# WAB_1x4_top.net
KiCad netlist of a schematic drawn in Altium Designer
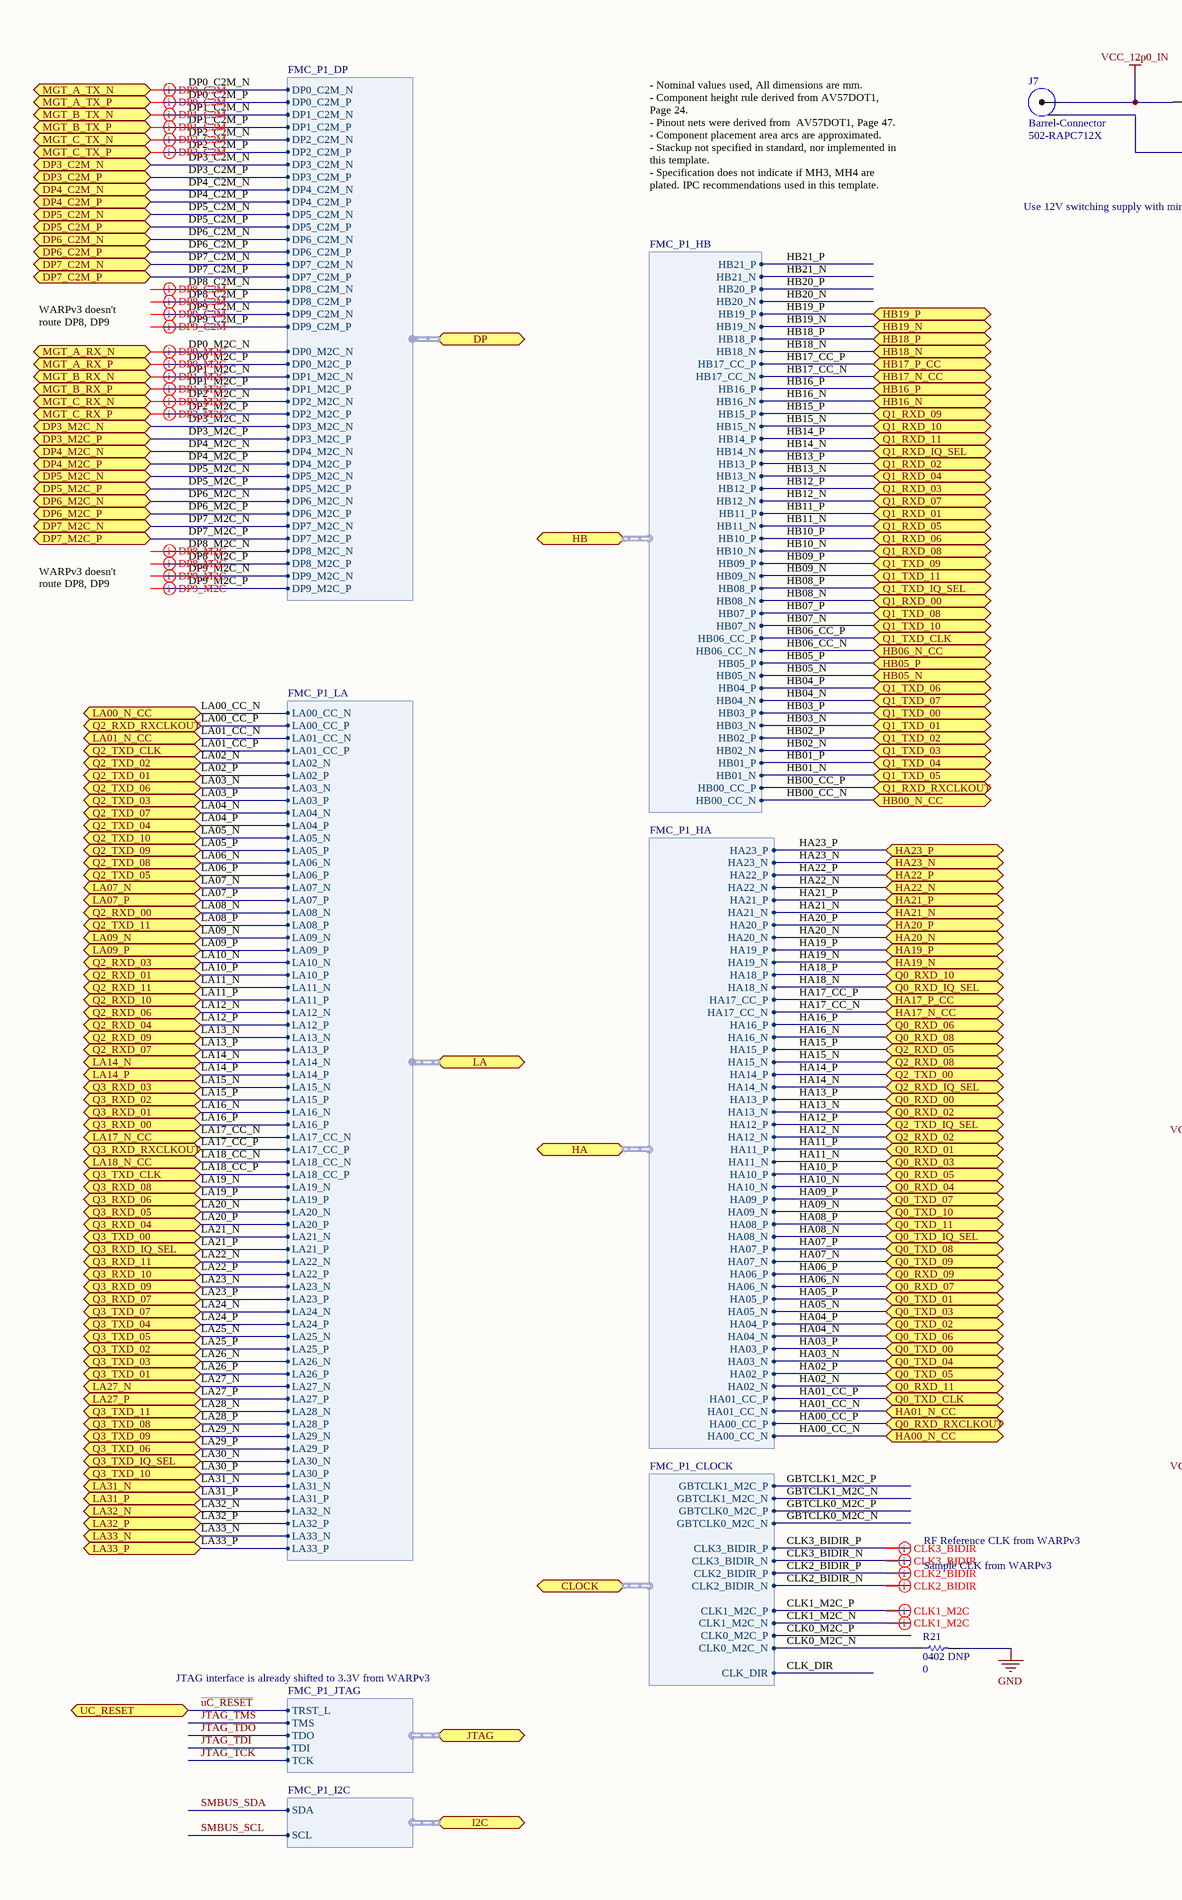
[diagram p0: WAB_1x4_top.SchDoc, left]
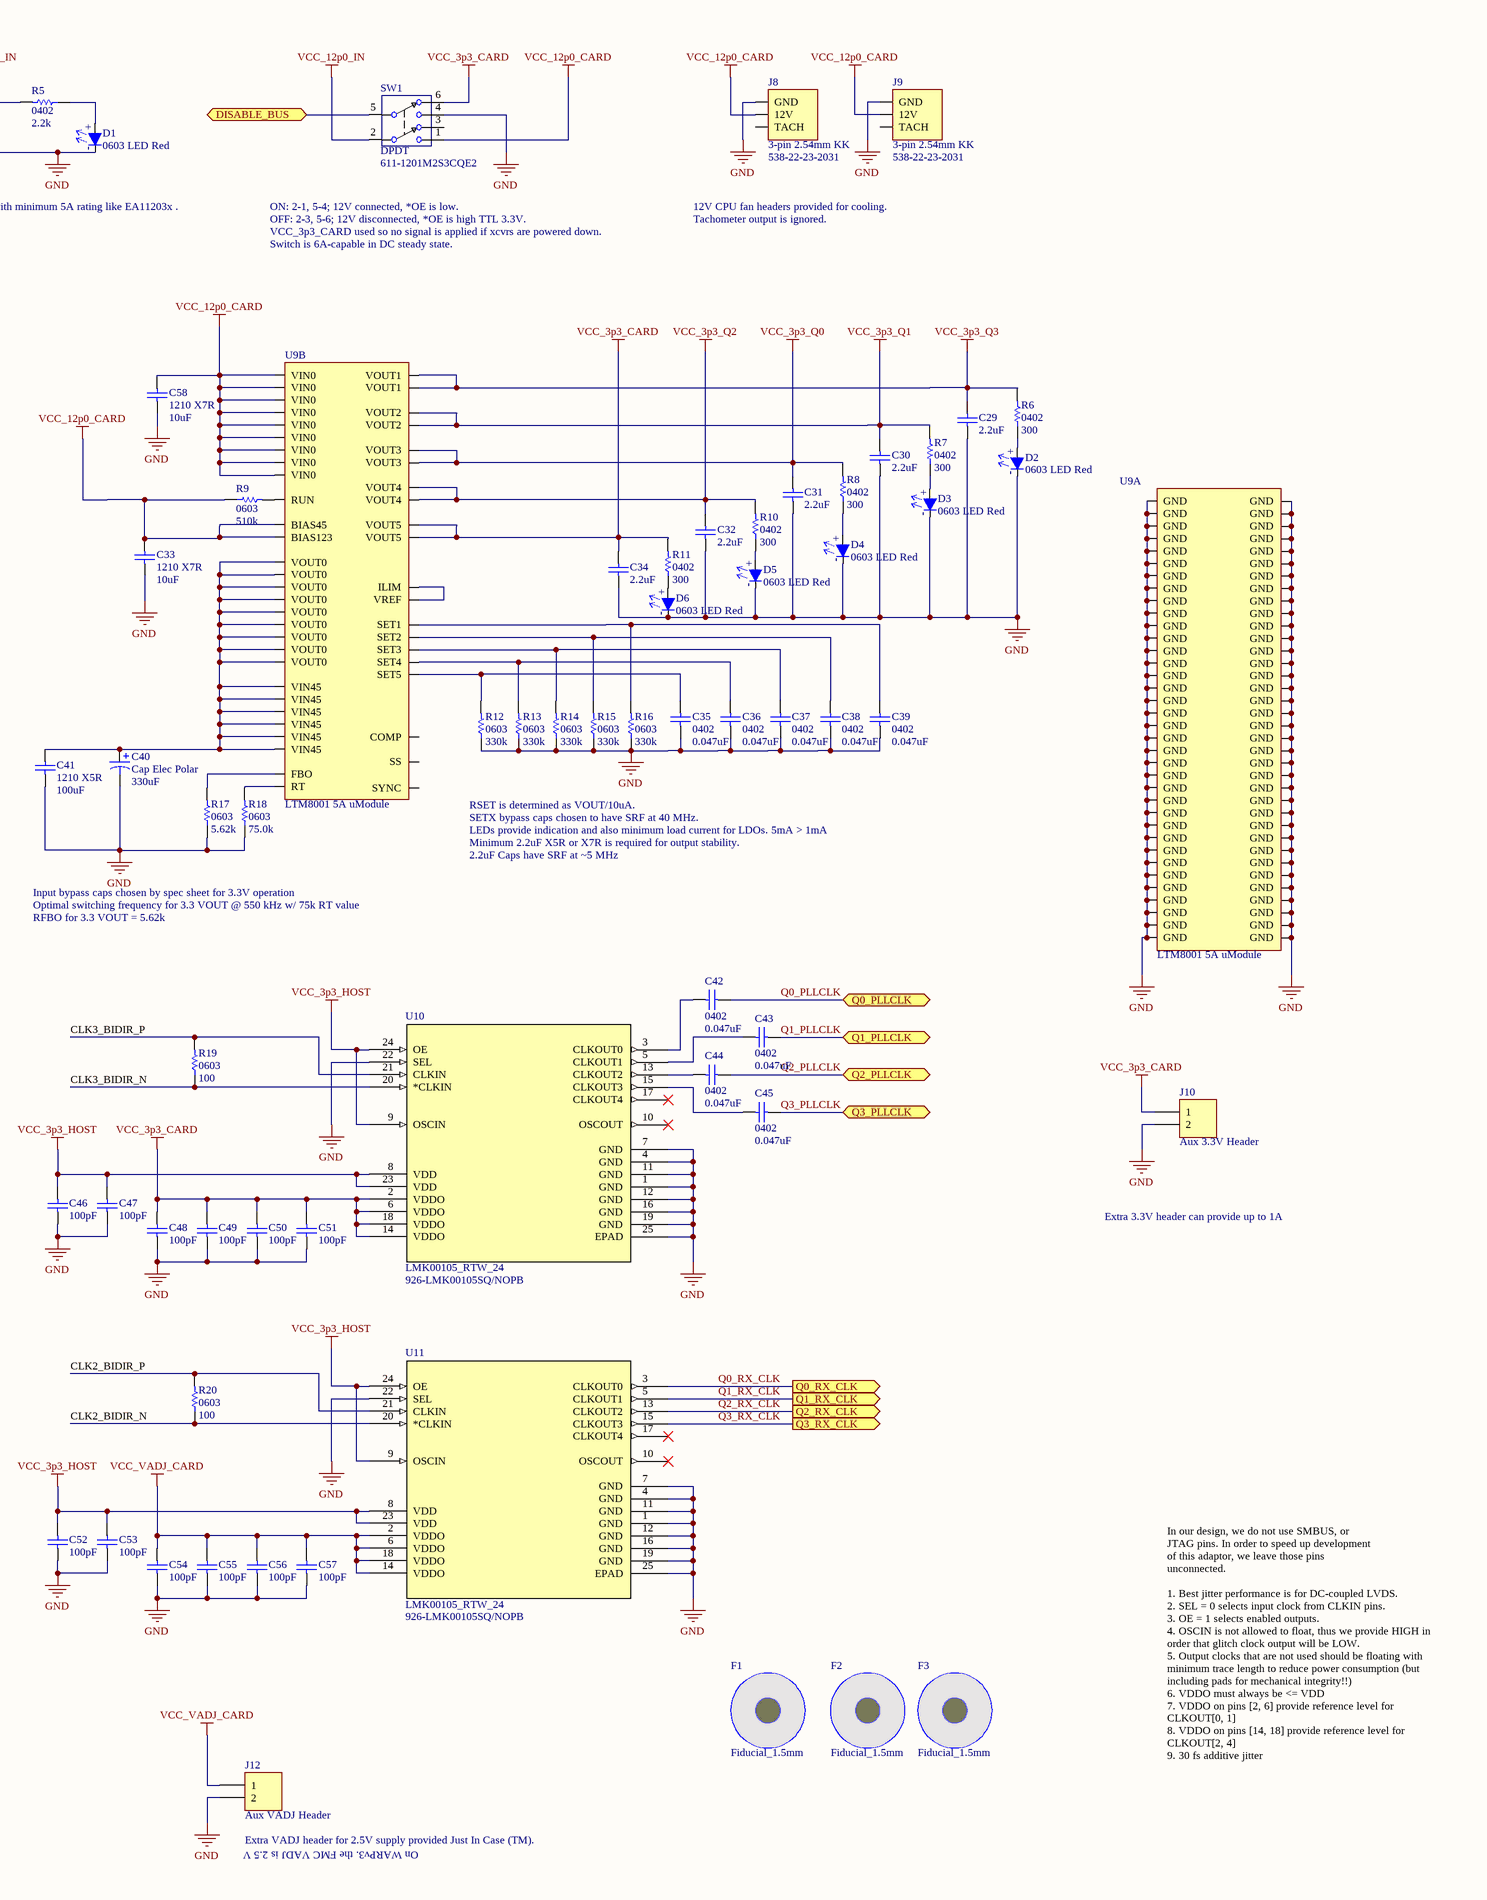
[diagram p1: WAB_1x4_top.SchDoc, right]

(export (version "E")
  (design (tool "Eeschema 10.0.6"))
  (components
    (comp (ref "C29")
      (value "2.2uF")
      (footprint "0402_SMT_CAP")
      (description "0402 SMT Capacitor")
      (fields (field (name "Comment") "0402"))
      (libsource (lib "RNG_Parts") (part "Cap_0402"))
    )
    (comp (ref "C30")
      (value "2.2uF")
      (footprint "0402_SMT_CAP")
      (description "0402 SMT Capacitor")
      (fields (field (name "Comment") "0402"))
      (libsource (lib "RNG_Parts") (part "Cap_0402"))
    )
    (comp (ref "C31")
      (value "2.2uF")
      (footprint "0402_SMT_CAP")
      (description "0402 SMT Capacitor")
      (fields (field (name "Comment") "0402"))
      (libsource (lib "RNG_Parts") (part "Cap_0402"))
    )
    (comp (ref "C32")
      (value "2.2uF")
      (footprint "0402_SMT_CAP")
      (description "0402 SMT Capacitor")
      (fields (field (name "Comment") "0402"))
      (libsource (lib "RNG_Parts") (part "Cap_0402"))
    )
    (comp (ref "C33")
      (value "1210 X7R")
      (footprint "1210_Chip_Cap")
      (description "1210 SMT Capacitor")
      (fields (field (name "ALTIUM_VALUE") "10uF"))
      (libsource (lib "RNG_Parts") (part "Cap_1210"))
    )
    (comp (ref "C34")
      (value "2.2uF")
      (footprint "0402_SMT_CAP")
      (description "0402 SMT Capacitor")
      (fields (field (name "Comment") "0402"))
      (libsource (lib "RNG_Parts") (part "Cap_0402"))
    )
    (comp (ref "C35")
      (value "0402")
      (footprint "0402_SMT_CAP")
      (description "0402 SMT Capacitor")
      (fields (field (name "ALTIUM_VALUE") "0.047uF"))
      (libsource (lib "RNG_Parts") (part "Cap_0402"))
    )
    (comp (ref "C36")
      (value "0402")
      (footprint "0402_SMT_CAP")
      (description "0402 SMT Capacitor")
      (fields (field (name "ALTIUM_VALUE") "0.047uF"))
      (libsource (lib "RNG_Parts") (part "Cap_0402"))
    )
    (comp (ref "C37")
      (value "0402")
      (footprint "0402_SMT_CAP")
      (description "0402 SMT Capacitor")
      (fields (field (name "ALTIUM_VALUE") "0.047uF"))
      (libsource (lib "RNG_Parts") (part "Cap_0402"))
    )
    (comp (ref "C38")
      (value "0402")
      (footprint "0402_SMT_CAP")
      (description "0402 SMT Capacitor")
      (fields (field (name "ALTIUM_VALUE") "0.047uF"))
      (libsource (lib "RNG_Parts") (part "Cap_0402"))
    )
    (comp (ref "C39")
      (value "0402")
      (footprint "0402_SMT_CAP")
      (description "0402 SMT Capacitor")
      (fields (field (name "ALTIUM_VALUE") "0.047uF"))
      (libsource (lib "RNG_Parts") (part "Cap_0402"))
    )
    (comp (ref "C40")
      (value "Cap Elec Polar")
      (footprint "RNG_Footprints:OSCON-SVPC-C6-V3_V2")
      (description "Polarized Capacitor (SMT Electrolytic)")
      (fields (field (name "ALTIUM_VALUE") "330uF") (field (name "PUBLISHER") "Altium Limited"))
      (libsource (lib "Miscellaneous Devices") (part "Cap Pol3"))
    )
    (comp (ref "C41")
      (value "1210 X5R")
      (footprint "1210_Chip_Cap")
      (description "1210 SMT Capacitor")
      (fields (field (name "ALTIUM_VALUE") "100uF"))
      (libsource (lib "RNG_Parts") (part "Cap_1210"))
    )
    (comp (ref "C42")
      (value "0402")
      (footprint "0402_SMT_CAP")
      (description "0402 SMT Capacitor")
      (fields (field (name "ALTIUM_VALUE") "0.047uF"))
      (libsource (lib "RNG_Parts") (part "Cap_0402"))
    )
    (comp (ref "C43")
      (value "0402")
      (footprint "0402_SMT_CAP")
      (description "0402 SMT Capacitor")
      (fields (field (name "ALTIUM_VALUE") "0.047uF"))
      (libsource (lib "RNG_Parts") (part "Cap_0402"))
    )
    (comp (ref "C44")
      (value "0402")
      (footprint "0402_SMT_CAP")
      (description "0402 SMT Capacitor")
      (fields (field (name "ALTIUM_VALUE") "0.047uF"))
      (libsource (lib "RNG_Parts") (part "Cap_0402"))
    )
    (comp (ref "C45")
      (value "0402")
      (footprint "0402_SMT_CAP")
      (description "0402 SMT Capacitor")
      (fields (field (name "ALTIUM_VALUE") "0.047uF"))
      (libsource (lib "RNG_Parts") (part "Cap_0402"))
    )
    (comp (ref "C46")
      (value "100pF")
      (footprint "0603_SMT_CAP")
      (description "0603 SMT Capacitor")
      (fields (field (name "Comment") "0603"))
      (libsource (lib "RNG_Parts") (part "Cap_0603"))
    )
    (comp (ref "C47")
      (value "100pF")
      (footprint "0603_SMT_CAP")
      (description "0603 SMT Capacitor")
      (fields (field (name "Comment") "0603"))
      (libsource (lib "RNG_Parts") (part "Cap_0603"))
    )
    (comp (ref "C48")
      (value "100pF")
      (footprint "0603_SMT_CAP")
      (description "0603 SMT Capacitor")
      (fields (field (name "Comment") "0603"))
      (libsource (lib "RNG_Parts") (part "Cap_0603"))
    )
    (comp (ref "C49")
      (value "100pF")
      (footprint "0603_SMT_CAP")
      (description "0603 SMT Capacitor")
      (fields (field (name "Comment") "0603"))
      (libsource (lib "RNG_Parts") (part "Cap_0603"))
    )
    (comp (ref "C50")
      (value "100pF")
      (footprint "0603_SMT_CAP")
      (description "0603 SMT Capacitor")
      (fields (field (name "Comment") "0603"))
      (libsource (lib "RNG_Parts") (part "Cap_0603"))
    )
    (comp (ref "C51")
      (value "100pF")
      (footprint "0603_SMT_CAP")
      (description "0603 SMT Capacitor")
      (fields (field (name "Comment") "0603"))
      (libsource (lib "RNG_Parts") (part "Cap_0603"))
    )
    (comp (ref "C52")
      (value "100pF")
      (footprint "0603_SMT_CAP")
      (description "0603 SMT Capacitor")
      (fields (field (name "Comment") "0603"))
      (libsource (lib "RNG_Parts") (part "Cap_0603"))
    )
    (comp (ref "C53")
      (value "100pF")
      (footprint "0603_SMT_CAP")
      (description "0603 SMT Capacitor")
      (fields (field (name "Comment") "0603"))
      (libsource (lib "RNG_Parts") (part "Cap_0603"))
    )
    (comp (ref "C54")
      (value "100pF")
      (footprint "0603_SMT_CAP")
      (description "0603 SMT Capacitor")
      (fields (field (name "Comment") "0603"))
      (libsource (lib "RNG_Parts") (part "Cap_0603"))
    )
    (comp (ref "C55")
      (value "100pF")
      (footprint "0603_SMT_CAP")
      (description "0603 SMT Capacitor")
      (fields (field (name "Comment") "0603"))
      (libsource (lib "RNG_Parts") (part "Cap_0603"))
    )
    (comp (ref "C56")
      (value "100pF")
      (footprint "0603_SMT_CAP")
      (description "0603 SMT Capacitor")
      (fields (field (name "Comment") "0603"))
      (libsource (lib "RNG_Parts") (part "Cap_0603"))
    )
    (comp (ref "C57")
      (value "100pF")
      (footprint "0603_SMT_CAP")
      (description "0603 SMT Capacitor")
      (fields (field (name "Comment") "0603"))
      (libsource (lib "RNG_Parts") (part "Cap_0603"))
    )
    (comp (ref "C58")
      (value "1210 X7R")
      (footprint "1210_Chip_Cap")
      (description "1210 SMT Capacitor")
      (fields (field (name "ALTIUM_VALUE") "10uF"))
      (libsource (lib "RNG_Parts") (part "Cap_1210"))
    )
    (comp (ref "D1")
      (value "0603 LED Red")
      (footprint "0603_SMT_LED")
      (description "0603 LED with Polar Markings")
      (libsource (lib "RNG_Parts") (part "LED_0603_Red"))
    )
    (comp (ref "D2")
      (value "0603 LED Red")
      (footprint "0603_SMT_LED")
      (description "0603 LED with Polar Markings")
      (libsource (lib "RNG_Parts") (part "LED_0603_Red"))
    )
    (comp (ref "D3")
      (value "0603 LED Red")
      (footprint "0603_SMT_LED")
      (description "0603 LED with Polar Markings")
      (libsource (lib "RNG_Parts") (part "LED_0603_Red"))
    )
    (comp (ref "D4")
      (value "0603 LED Red")
      (footprint "0603_SMT_LED")
      (description "0603 LED with Polar Markings")
      (libsource (lib "RNG_Parts") (part "LED_0603_Red"))
    )
    (comp (ref "D5")
      (value "0603 LED Red")
      (footprint "0603_SMT_LED")
      (description "0603 LED with Polar Markings")
      (libsource (lib "RNG_Parts") (part "LED_0603_Red"))
    )
    (comp (ref "D6")
      (value "0603 LED Red")
      (footprint "0603_SMT_LED")
      (description "0603 LED with Polar Markings")
      (libsource (lib "RNG_Parts") (part "LED_0603_Red"))
    )
    (comp (ref "F1")
      (value "Fiducial_1.5mm")
      (footprint "1.5mm_FIDUCIAL_v4")
      (libsource (lib "RNG_Parts") (part "Fiducial_1.5mm"))
    )
    (comp (ref "F2")
      (value "Fiducial_1.5mm")
      (footprint "1.5mm_FIDUCIAL_v4")
      (libsource (lib "RNG_Parts") (part "Fiducial_1.5mm"))
    )
    (comp (ref "F3")
      (value "Fiducial_1.5mm")
      (footprint "1.5mm_FIDUCIAL_v4")
      (libsource (lib "RNG_Parts") (part "Fiducial_1.5mm"))
    )
    (comp (ref "J7")
      (value "Barrel-Connector")
      (footprint "RAPC712X")
      (description "2.5mm Barrel Jack Rt-Angle Thru-Mount")
      (fields (field (name "SUPPLIER PART NUMBER 1") "502-RAPC712X"))
      (libsource (lib "RNG_Parts") (part "Barrel-Connector-RAPC712X"))
    )
    (comp (ref "J8")
      (value "3-pin 2.54mm KK")
      (footprint "3-Pin_Fan_Header")
      (description "Molex KK Series PCB Mount 3-pin 2.54mm Fan Header")
      (fields (field (name "SUPPLIER PART NUMBER 1") "538-22-23-2031"))
      (libsource (lib "RNG_Parts") (part "3-Pin 2.54mm Fan Header"))
    )
    (comp (ref "J9")
      (value "3-pin 2.54mm KK")
      (footprint "3-Pin_Fan_Header")
      (description "Molex KK Series PCB Mount 3-pin 2.54mm Fan Header")
      (fields (field (name "SUPPLIER PART NUMBER 1") "538-22-23-2031"))
      (libsource (lib "RNG_Parts") (part "3-Pin 2.54mm Fan Header"))
    )
    (comp (ref "J10")
      (value "Aux 3.3V Header")
      (footprint "HDR1X2")
      (description "Header, 2-Pin")
      (fields (field (name "PUBLISHER") "Altium Limited"))
      (libsource (lib "Miscellaneous Connectors") (part "Header 2"))
    )
    (comp (ref "J12")
      (value "Aux VADJ Header")
      (footprint "HDR1X2")
      (description "Header, 2-Pin")
      (fields (field (name "PUBLISHER") "Altium Limited"))
      (libsource (lib "Miscellaneous Connectors") (part "Header 2"))
    )
    (comp (ref "R5")
      (value "0402")
      (footprint "0402_SMT_RES")
      (description "0402 SMT Resistor")
      (fields (field (name "ALTIUM_VALUE") "2.2k"))
      (libsource (lib "RNG_Parts") (part "Res_0402"))
    )
    (comp (ref "R6")
      (value "0402")
      (footprint "0402_SMT_RES")
      (description "0402 SMT Resistor")
      (fields (field (name "ALTIUM_VALUE") "300"))
      (libsource (lib "RNG_Parts") (part "Res_0402"))
    )
    (comp (ref "R7")
      (value "0402")
      (footprint "0402_SMT_RES")
      (description "0402 SMT Resistor")
      (fields (field (name "ALTIUM_VALUE") "300"))
      (libsource (lib "RNG_Parts") (part "Res_0402"))
    )
    (comp (ref "R8")
      (value "0402")
      (footprint "0402_SMT_RES")
      (description "0402 SMT Resistor")
      (fields (field (name "ALTIUM_VALUE") "300"))
      (libsource (lib "RNG_Parts") (part "Res_0402"))
    )
    (comp (ref "R9")
      (value "0603")
      (footprint "0603_SMT_RES")
      (description "0603 SMT Resistor")
      (fields (field (name "ALTIUM_VALUE") "510k"))
      (libsource (lib "RNG_Parts") (part "Res_0603"))
    )
    (comp (ref "R10")
      (value "0402")
      (footprint "0402_SMT_RES")
      (description "0402 SMT Resistor")
      (fields (field (name "ALTIUM_VALUE") "300"))
      (libsource (lib "RNG_Parts") (part "Res_0402"))
    )
    (comp (ref "R11")
      (value "0402")
      (footprint "0402_SMT_RES")
      (description "0402 SMT Resistor")
      (fields (field (name "ALTIUM_VALUE") "300"))
      (libsource (lib "RNG_Parts") (part "Res_0402"))
    )
    (comp (ref "R12")
      (value "0603")
      (footprint "0603_SMT_RES")
      (description "0603 SMT Resistor")
      (fields (field (name "ALTIUM_VALUE") "330k"))
      (libsource (lib "RNG_Parts") (part "Res_0603"))
    )
    (comp (ref "R13")
      (value "0603")
      (footprint "0603_SMT_RES")
      (description "0603 SMT Resistor")
      (fields (field (name "ALTIUM_VALUE") "330k"))
      (libsource (lib "RNG_Parts") (part "Res_0603"))
    )
    (comp (ref "R14")
      (value "0603")
      (footprint "0603_SMT_RES")
      (description "0603 SMT Resistor")
      (fields (field (name "ALTIUM_VALUE") "330k"))
      (libsource (lib "RNG_Parts") (part "Res_0603"))
    )
    (comp (ref "R15")
      (value "0603")
      (footprint "0603_SMT_RES")
      (description "0603 SMT Resistor")
      (fields (field (name "ALTIUM_VALUE") "330k"))
      (libsource (lib "RNG_Parts") (part "Res_0603"))
    )
    (comp (ref "R16")
      (value "0603")
      (footprint "0603_SMT_RES")
      (description "0603 SMT Resistor")
      (fields (field (name "ALTIUM_VALUE") "330k"))
      (libsource (lib "RNG_Parts") (part "Res_0603"))
    )
    (comp (ref "R17")
      (value "0603")
      (footprint "0603_SMT_RES")
      (description "0603 SMT Resistor")
      (fields (field (name "ALTIUM_VALUE") "5.62k"))
      (libsource (lib "RNG_Parts") (part "Res_0603"))
    )
    (comp (ref "R18")
      (value "0603")
      (footprint "0603_SMT_RES")
      (description "0603 SMT Resistor")
      (fields (field (name "ALTIUM_VALUE") "75.0k"))
      (libsource (lib "RNG_Parts") (part "Res_0603"))
    )
    (comp (ref "R19")
      (value "0603")
      (footprint "0603_SMT_RES")
      (description "0603 SMT Resistor")
      (fields (field (name "ALTIUM_VALUE") "100"))
      (libsource (lib "RNG_Parts") (part "Res_0603"))
    )
    (comp (ref "R20")
      (value "0603")
      (footprint "0603_SMT_RES")
      (description "0603 SMT Resistor")
      (fields (field (name "ALTIUM_VALUE") "100"))
      (libsource (lib "RNG_Parts") (part "Res_0603"))
    )
    (comp (ref "R21")
      (value "0402 DNP")
      (footprint "0402_SMT_RES")
      (description "0402 SMT Resistor")
      (fields (field (name "ALTIUM_VALUE") "0"))
      (libsource (lib "RNG_Parts") (part "Res_0402"))
    )
    (comp (ref "SW1")
      (value "DPDT")
      (footprint "1201-M2-S3-C-QE2")
      (description "DPDT 6A Slide Switch C&K Thru")
      (fields (field (name "SUPPLIER PART NUMBER 1") "611-1201M2S3CQE2"))
      (libsource (lib "RNG_Parts") (part "1201-M2-S2-C-X-XXX"))
    )
    (comp (ref "U9")
      (value "LTM8001 5A uModule")
      (footprint "BGA121_15x15x3.42")
      (description "36Vin, 5A uModule Regulator with 5-Output Configurable LDO Array")
      (libsource (lib "RNG_Parts") (part "LTM8001_BGA121"))
    )
    (comp (ref "U10")
      (value "LMK00105_RTW_24")
      (footprint "RTW24_3")
      (description "TI Universal-to-CMOS 5-Output Clock Buffer")
      (fields
        (field (name "MANUFACTURER_PART_NUMBER") "lmk00105_rtw_24")
        (field (name "SUPPLIER PART NUMBER 1") "926-LMK00105SQ/NOPB")
      )
      (libsource (lib "RNG_Parts") (part "LMK00105_RTW_24"))
    )
    (comp (ref "U11")
      (value "LMK00105_RTW_24")
      (footprint "RTW24_3")
      (description "TI Universal-to-CMOS 5-Output Clock Buffer")
      (fields
        (field (name "MANUFACTURER_PART_NUMBER") "lmk00105_rtw_24")
        (field (name "SUPPLIER PART NUMBER 1") "926-LMK00105SQ/NOPB")
      )
      (libsource (lib "RNG_Parts") (part "LMK00105_RTW_24"))
    )
  )
  (nets
    (net (code "8") (name "/CLK0_M2C_N") (class "Default")
      (node (ref "R21") (pin "1") (pinfunction "1_1") (pintype "passive"))
    )
    (net (code "12") (name "/CLK2_BIDIR_N") (class "Default")
      (node (ref "R20") (pin "1") (pinfunction "1_1") (pintype "passive"))
      (node (ref "U11") (pin "20") (pinfunction "*CLKIN_20") (pintype "input"))
    )
    (net (code "13") (name "/CLK2_BIDIR_P") (class "Default")
      (node (ref "R20") (pin "2") (pinfunction "2_2") (pintype "passive"))
      (node (ref "U11") (pin "21") (pinfunction "CLKIN_21") (pintype "input"))
    )
    (net (code "14") (name "/CLK3_BIDIR_N") (class "Default")
      (node (ref "R19") (pin "1") (pinfunction "1_1") (pintype "passive"))
      (node (ref "U10") (pin "20") (pinfunction "*CLKIN_20") (pintype "input"))
    )
    (net (code "15") (name "/CLK3_BIDIR_P") (class "Default")
      (node (ref "R19") (pin "2") (pinfunction "2_2") (pintype "passive"))
      (node (ref "U10") (pin "21") (pinfunction "CLKIN_21") (pintype "input"))
    )
    (net (code "17") (name "/DISABLE_BUS") (class "Default")
      (node (ref "SW1") (pin "5") (pinfunction "5_5") (pintype "passive"))
    )
    (net (code "226") (name "/Q0_PLLCLK") (class "Default")
      (node (ref "C42") (pin "2") (pinfunction "2_2") (pintype "passive"))
    )
    (net (code "227") (name "/Q0_RX_CLK") (class "Default")
      (node (ref "U11") (pin "3") (pinfunction "CLKOUT0_3") (pintype "output"))
    )
    (net (code "228") (name "/Q1_PLLCLK") (class "Default")
      (node (ref "C43") (pin "2") (pinfunction "2_2") (pintype "passive"))
    )
    (net (code "229") (name "/Q1_RX_CLK") (class "Default")
      (node (ref "U11") (pin "5") (pinfunction "CLKOUT1_5") (pintype "output"))
    )
    (net (code "230") (name "/Q2_PLLCLK") (class "Default")
      (node (ref "C44") (pin "2") (pinfunction "2_2") (pintype "passive"))
    )
    (net (code "231") (name "/Q2_RX_CLK") (class "Default")
      (node (ref "U11") (pin "13") (pinfunction "CLKOUT2_13") (pintype "output"))
    )
    (net (code "232") (name "/Q3_PLLCLK") (class "Default")
      (node (ref "C45") (pin "2") (pinfunction "2_2") (pintype "passive"))
    )
    (net (code "233") (name "/Q3_RX_CLK") (class "Default")
      (node (ref "U11") (pin "15") (pinfunction "CLKOUT3_15") (pintype "output"))
    )
    (net (code "244") (name "GND") (class "Default")
      (node (ref "C29") (pin "1") (pinfunction "1_1") (pintype "passive"))
      (node (ref "C30") (pin "1") (pinfunction "1_1") (pintype "passive"))
      (node (ref "C31") (pin "1") (pinfunction "1_1") (pintype "passive"))
      (node (ref "C32") (pin "1") (pinfunction "1_1") (pintype "passive"))
      (node (ref "C33") (pin "2") (pinfunction "2_2") (pintype "passive"))
      (node (ref "C34") (pin "1") (pinfunction "1_1") (pintype "passive"))
      (node (ref "C35") (pin "2") (pinfunction "2_2") (pintype "passive"))
      (node (ref "C36") (pin "2") (pinfunction "2_2") (pintype "passive"))
      (node (ref "C37") (pin "2") (pinfunction "2_2") (pintype "passive"))
      (node (ref "C38") (pin "2") (pinfunction "2_2") (pintype "passive"))
      (node (ref "C39") (pin "2") (pinfunction "2_2") (pintype "passive"))
      (node (ref "C40") (pin "2") (pinfunction "2_2") (pintype "passive"))
      (node (ref "C41") (pin "2") (pinfunction "2_2") (pintype "passive"))
      (node (ref "C46") (pin "1") (pinfunction "1_1") (pintype "passive"))
      (node (ref "C47") (pin "1") (pinfunction "1_1") (pintype "passive"))
      (node (ref "C48") (pin "1") (pinfunction "1_1") (pintype "passive"))
      (node (ref "C49") (pin "1") (pinfunction "1_1") (pintype "passive"))
      (node (ref "C50") (pin "1") (pinfunction "1_1") (pintype "passive"))
      (node (ref "C51") (pin "1") (pinfunction "1_1") (pintype "passive"))
      (node (ref "C52") (pin "1") (pinfunction "1_1") (pintype "passive"))
      (node (ref "C53") (pin "1") (pinfunction "1_1") (pintype "passive"))
      (node (ref "C54") (pin "1") (pinfunction "1_1") (pintype "passive"))
      (node (ref "C55") (pin "1") (pinfunction "1_1") (pintype "passive"))
      (node (ref "C56") (pin "1") (pinfunction "1_1") (pintype "passive"))
      (node (ref "C57") (pin "1") (pinfunction "1_1") (pintype "passive"))
      (node (ref "C58") (pin "2") (pinfunction "2_2") (pintype "passive"))
      (node (ref "D1") (pin "2") (pinfunction "N_2") (pintype "passive"))
      (node (ref "D2") (pin "2") (pinfunction "N_2") (pintype "passive"))
      (node (ref "D3") (pin "2") (pinfunction "N_2") (pintype "passive"))
      (node (ref "D4") (pin "2") (pinfunction "N_2") (pintype "passive"))
      (node (ref "D5") (pin "2") (pinfunction "N_2") (pintype "passive"))
      (node (ref "D6") (pin "2") (pinfunction "N_2") (pintype "passive"))
      (node (ref "J10") (pin "2") (pinfunction "2_2") (pintype "passive"))
      (node (ref "J12") (pin "2") (pinfunction "2_2") (pintype "passive"))
      (node (ref "J7") (pin "1") (pinfunction "GND_1") (pintype "power_in"))
      (node (ref "J8") (pin "1") (pinfunction "GND_1") (pintype "power_in"))
      (node (ref "J9") (pin "1") (pinfunction "GND_1") (pintype "power_in"))
      (node (ref "R12") (pin "1") (pinfunction "1_1") (pintype "passive"))
      (node (ref "R13") (pin "1") (pinfunction "1_1") (pintype "passive"))
      (node (ref "R14") (pin "1") (pinfunction "1_1") (pintype "passive"))
      (node (ref "R15") (pin "1") (pinfunction "1_1") (pintype "passive"))
      (node (ref "R16") (pin "1") (pinfunction "1_1") (pintype "passive"))
      (node (ref "R17") (pin "1") (pinfunction "1_1") (pintype "passive"))
      (node (ref "R18") (pin "1") (pinfunction "1_1") (pintype "passive"))
      (node (ref "R21") (pin "2") (pinfunction "2_2") (pintype "passive"))
      (node (ref "SW1") (pin "4") (pinfunction "4_4") (pintype "passive"))
      (node (ref "U10") (pin "1") (pinfunction "GND_1") (pintype "power_in"))
      (node (ref "U10") (pin "11") (pinfunction "GND_11") (pintype "power_in"))
      (node (ref "U10") (pin "12") (pinfunction "GND_12") (pintype "power_in"))
      (node (ref "U10") (pin "16") (pinfunction "GND_16") (pintype "power_in"))
      (node (ref "U10") (pin "19") (pinfunction "GND_19") (pintype "power_in"))
      (node (ref "U10") (pin "22") (pinfunction "SEL_22") (pintype "input"))
      (node (ref "U10") (pin "25") (pinfunction "EPAD_25") (pintype "passive"))
      (node (ref "U10") (pin "4") (pinfunction "GND_4") (pintype "power_in"))
      (node (ref "U10") (pin "7") (pinfunction "GND_7") (pintype "power_in"))
      (node (ref "U11") (pin "1") (pinfunction "GND_1") (pintype "power_in"))
      (node (ref "U11") (pin "11") (pinfunction "GND_11") (pintype "power_in"))
      (node (ref "U11") (pin "12") (pinfunction "GND_12") (pintype "power_in"))
      (node (ref "U11") (pin "16") (pinfunction "GND_16") (pintype "power_in"))
      (node (ref "U11") (pin "19") (pinfunction "GND_19") (pintype "power_in"))
      (node (ref "U11") (pin "22") (pinfunction "SEL_22") (pintype "input"))
      (node (ref "U11") (pin "25") (pinfunction "EPAD_25") (pintype "passive"))
      (node (ref "U11") (pin "4") (pinfunction "GND_4") (pintype "power_in"))
      (node (ref "U11") (pin "7") (pinfunction "GND_7") (pintype "power_in"))
      (node (ref "U9") (pin "A1") (pinfunction "GND_A1") (pintype "passive"))
      (node (ref "U9") (pin "A2") (pinfunction "GND_A2") (pintype "passive"))
      (node (ref "U9") (pin "B1") (pinfunction "GND_B1") (pintype "passive"))
      (node (ref "U9") (pin "B10") (pinfunction "GND_B10") (pintype "passive"))
      (node (ref "U9") (pin "B2") (pinfunction "GND_B2") (pintype "passive"))
      (node (ref "U9") (pin "B9") (pinfunction "GND_B9") (pintype "passive"))
      (node (ref "U9") (pin "C1") (pinfunction "GND_C1") (pintype "passive"))
      (node (ref "U9") (pin "C10") (pinfunction "GND_C10") (pintype "passive"))
      (node (ref "U9") (pin "C2") (pinfunction "GND_C2") (pintype "passive"))
      (node (ref "U9") (pin "C8") (pinfunction "GND_C8") (pintype "passive"))
      (node (ref "U9") (pin "C9") (pinfunction "GND_C9") (pintype "passive"))
      (node (ref "U9") (pin "D1") (pinfunction "GND_D1") (pintype "passive"))
      (node (ref "U9") (pin "D10") (pinfunction "GND_D10") (pintype "passive"))
      (node (ref "U9") (pin "D2") (pinfunction "GND_D2") (pintype "passive"))
      (node (ref "U9") (pin "D3") (pinfunction "GND_D3") (pintype "passive"))
      (node (ref "U9") (pin "D4") (pinfunction "GND_D4") (pintype "passive"))
      (node (ref "U9") (pin "D5") (pinfunction "GND_D5") (pintype "passive"))
      (node (ref "U9") (pin "D6") (pinfunction "GND_D6") (pintype "passive"))
      (node (ref "U9") (pin "D7") (pinfunction "GND_D7") (pintype "passive"))
      (node (ref "U9") (pin "D8") (pinfunction "GND_D8") (pintype "passive"))
      (node (ref "U9") (pin "D9") (pinfunction "GND_D9") (pintype "passive"))
      (node (ref "U9") (pin "E1") (pinfunction "GND_E1") (pintype "passive"))
      (node (ref "U9") (pin "E10") (pinfunction "GND_E10") (pintype "passive"))
      (node (ref "U9") (pin "E2") (pinfunction "GND_E2") (pintype "passive"))
      (node (ref "U9") (pin "E3") (pinfunction "GND_E3") (pintype "passive"))
      (node (ref "U9") (pin "E4") (pinfunction "GND_E4") (pintype "passive"))
      (node (ref "U9") (pin "E5") (pinfunction "GND_E5") (pintype "passive"))
      (node (ref "U9") (pin "E6") (pinfunction "GND_E6") (pintype "passive"))
      (node (ref "U9") (pin "E7") (pinfunction "GND_E7") (pintype "passive"))
      (node (ref "U9") (pin "E8") (pinfunction "GND_E8") (pintype "passive"))
      (node (ref "U9") (pin "E9") (pinfunction "GND_E9") (pintype "passive"))
      (node (ref "U9") (pin "F1") (pinfunction "GND_F1") (pintype "passive"))
      (node (ref "U9") (pin "F10") (pinfunction "GND_F10") (pintype "passive"))
      (node (ref "U9") (pin "F2") (pinfunction "GND_F2") (pintype "passive"))
      (node (ref "U9") (pin "F3") (pinfunction "GND_F3") (pintype "passive"))
      (node (ref "U9") (pin "F4") (pinfunction "GND_F4") (pintype "passive"))
      (node (ref "U9") (pin "F5") (pinfunction "GND_F5") (pintype "passive"))
      (node (ref "U9") (pin "F6") (pinfunction "GND_F6") (pintype "passive"))
      (node (ref "U9") (pin "F7") (pinfunction "GND_F7") (pintype "passive"))
      (node (ref "U9") (pin "F8") (pinfunction "GND_F8") (pintype "passive"))
      (node (ref "U9") (pin "F9") (pinfunction "GND_F9") (pintype "passive"))
      (node (ref "U9") (pin "G1") (pinfunction "GND_G1") (pintype "passive"))
      (node (ref "U9") (pin "G10") (pinfunction "GND_G10") (pintype "passive"))
      (node (ref "U9") (pin "G2") (pinfunction "GND_G2") (pintype "passive"))
      (node (ref "U9") (pin "G3") (pinfunction "GND_G3") (pintype "passive"))
      (node (ref "U9") (pin "G4") (pinfunction "GND_G4") (pintype "passive"))
      (node (ref "U9") (pin "G5") (pinfunction "GND_G5") (pintype "passive"))
      (node (ref "U9") (pin "G6") (pinfunction "GND_G6") (pintype "passive"))
      (node (ref "U9") (pin "G7") (pinfunction "GND_G7") (pintype "passive"))
      (node (ref "U9") (pin "G8") (pinfunction "GND_G8") (pintype "passive"))
      (node (ref "U9") (pin "G9") (pinfunction "GND_G9") (pintype "passive"))
      (node (ref "U9") (pin "H1") (pinfunction "GND_H1") (pintype "passive"))
      (node (ref "U9") (pin "H10") (pinfunction "GND_H10") (pintype "passive"))
      (node (ref "U9") (pin "H2") (pinfunction "GND_H2") (pintype "passive"))
      (node (ref "U9") (pin "H3") (pinfunction "GND_H3") (pintype "passive"))
      (node (ref "U9") (pin "H4") (pinfunction "GND_H4") (pintype "passive"))
      (node (ref "U9") (pin "H5") (pinfunction "GND_H5") (pintype "passive"))
      (node (ref "U9") (pin "H6") (pinfunction "GND_H6") (pintype "passive"))
      (node (ref "U9") (pin "H7") (pinfunction "GND_H7") (pintype "passive"))
      (node (ref "U9") (pin "H8") (pinfunction "GND_H8") (pintype "passive"))
      (node (ref "U9") (pin "H9") (pinfunction "GND_H9") (pintype "passive"))
      (node (ref "U9") (pin "J10") (pinfunction "GND_J10") (pintype "passive"))
      (node (ref "U9") (pin "J4") (pinfunction "GND_J4") (pintype "passive"))
      (node (ref "U9") (pin "J5") (pinfunction "GND_J5") (pintype "passive"))
      (node (ref "U9") (pin "J6") (pinfunction "GND_J6") (pintype "passive"))
      (node (ref "U9") (pin "J7") (pinfunction "GND_J7") (pintype "passive"))
      (node (ref "U9") (pin "J8") (pinfunction "GND_J8") (pintype "passive"))
      (node (ref "U9") (pin "J9") (pinfunction "GND_J9") (pintype "passive"))
      (node (ref "U9") (pin "K10") (pinfunction "GND_K10") (pintype "passive"))
      (node (ref "U9") (pin "K5") (pinfunction "GND_K5") (pintype "passive"))
      (node (ref "U9") (pin "K6") (pinfunction "GND_K6") (pintype "passive"))
      (node (ref "U9") (pin "K9") (pinfunction "GND_K9") (pintype "passive"))
    )
    (net (code "245") (name "Net-(C40-Pad1)") (class "Default")
      (node (ref "C40") (pin "1") (pinfunction "1_1") (pintype "passive"))
      (node (ref "C41") (pin "1") (pinfunction "1_1") (pintype "passive"))
      (node (ref "U9") (pin "A3") (pinfunction "VOUT0_A3") (pintype "power_in"))
      (node (ref "U9") (pin "A4") (pinfunction "VOUT0_A4") (pintype "power_in"))
      (node (ref "U9") (pin "A5") (pinfunction "VOUT0_A5") (pintype "power_in"))
      (node (ref "U9") (pin "A6") (pinfunction "VIN45_A6") (pintype "power_in"))
      (node (ref "U9") (pin "A7") (pinfunction "VIN45_A7") (pintype "power_in"))
      (node (ref "U9") (pin "B3") (pinfunction "VOUT0_B3") (pintype "power_in"))
      (node (ref "U9") (pin "B4") (pinfunction "VOUT0_B4") (pintype "power_in"))
      (node (ref "U9") (pin "B5") (pinfunction "VOUT0_B5") (pintype "power_in"))
      (node (ref "U9") (pin "B6") (pinfunction "VIN45_B6") (pintype "power_in"))
      (node (ref "U9") (pin "B7") (pinfunction "VIN45_B7") (pintype "power_in"))
      (node (ref "U9") (pin "C3") (pinfunction "VOUT0_C3") (pintype "power_in"))
      (node (ref "U9") (pin "C4") (pinfunction "VOUT0_C4") (pintype "power_in"))
      (node (ref "U9") (pin "C5") (pinfunction "VOUT0_C5") (pintype "power_in"))
      (node (ref "U9") (pin "C6") (pinfunction "VIN45_C6") (pintype "power_in"))
      (node (ref "U9") (pin "C7") (pinfunction "VIN45_C7") (pintype "power_in"))
    )
    (net (code "246") (name "Net-(D1-P)") (class "Default")
      (node (ref "D1") (pin "1") (pinfunction "P_1") (pintype "passive"))
      (node (ref "R5") (pin "1") (pinfunction "1_1") (pintype "passive"))
    )
    (net (code "247") (name "Net-(D2-P)") (class "Default")
      (node (ref "D2") (pin "1") (pinfunction "P_1") (pintype "passive"))
      (node (ref "R6") (pin "1") (pinfunction "1_1") (pintype "passive"))
    )
    (net (code "248") (name "Net-(D3-P)") (class "Default")
      (node (ref "D3") (pin "1") (pinfunction "P_1") (pintype "passive"))
      (node (ref "R7") (pin "1") (pinfunction "1_1") (pintype "passive"))
    )
    (net (code "249") (name "Net-(D4-P)") (class "Default")
      (node (ref "D4") (pin "1") (pinfunction "P_1") (pintype "passive"))
      (node (ref "R8") (pin "1") (pinfunction "1_1") (pintype "passive"))
    )
    (net (code "250") (name "Net-(D5-P)") (class "Default")
      (node (ref "D5") (pin "1") (pinfunction "P_1") (pintype "passive"))
      (node (ref "R10") (pin "1") (pinfunction "1_1") (pintype "passive"))
    )
    (net (code "251") (name "Net-(D6-P)") (class "Default")
      (node (ref "D6") (pin "1") (pinfunction "P_1") (pintype "passive"))
      (node (ref "R11") (pin "1") (pinfunction "1_1") (pintype "passive"))
    )
    (net (code "252") (name "Net-(U9B-FBO)") (class "Default")
      (node (ref "R17") (pin "2") (pinfunction "2_2") (pintype "passive"))
      (node (ref "U9") (pin "L5") (pinfunction "FBO_L5") (pintype "passive"))
    )
    (net (code "253") (name "Net-(U9B-ILIM)") (class "Default")
      (node (ref "U9") (pin "K8") (pinfunction "VREF_K8") (pintype "passive"))
      (node (ref "U9") (pin "L8") (pinfunction "ILIM_L8") (pintype "passive"))
    )
    (net (code "254") (name "Net-(U9B-RT)") (class "Default")
      (node (ref "R18") (pin "2") (pinfunction "2_2") (pintype "passive"))
      (node (ref "U9") (pin "L7") (pinfunction "RT_L7") (pintype "passive"))
    )
    (net (code "255") (name "Net-(U9B-RUN)") (class "Default")
      (node (ref "R9") (pin "2") (pinfunction "2_2") (pintype "passive"))
      (node (ref "U9") (pin "L4") (pinfunction "RUN_L4") (pintype "passive"))
    )
    (net (code "256") (name "Net-(U9B-SET1)") (class "Default")
      (node (ref "C39") (pin "1") (pinfunction "1_1") (pintype "passive"))
      (node (ref "R16") (pin "2") (pinfunction "2_2") (pintype "passive"))
      (node (ref "U9") (pin "L9") (pinfunction "SET1_L9") (pintype "passive"))
    )
    (net (code "257") (name "Net-(U9B-SET2)") (class "Default")
      (node (ref "C38") (pin "1") (pinfunction "1_1") (pintype "passive"))
      (node (ref "R15") (pin "2") (pinfunction "2_2") (pintype "passive"))
      (node (ref "U9") (pin "H11") (pinfunction "SET2_H11") (pintype "passive"))
    )
    (net (code "258") (name "Net-(U9B-SET3)") (class "Default")
      (node (ref "C37") (pin "1") (pinfunction "1_1") (pintype "passive"))
      (node (ref "R14") (pin "2") (pinfunction "2_2") (pintype "passive"))
      (node (ref "U9") (pin "G11") (pinfunction "SET3_G11") (pintype "passive"))
    )
    (net (code "259") (name "Net-(U9B-SET4)") (class "Default")
      (node (ref "C36") (pin "1") (pinfunction "1_1") (pintype "passive"))
      (node (ref "R13") (pin "2") (pinfunction "2_2") (pintype "passive"))
      (node (ref "U9") (pin "D11") (pinfunction "SET4_D11") (pintype "passive"))
    )
    (net (code "260") (name "Net-(U9B-SET5)") (class "Default")
      (node (ref "C35") (pin "1") (pinfunction "1_1") (pintype "passive"))
      (node (ref "R12") (pin "2") (pinfunction "2_2") (pintype "passive"))
      (node (ref "U9") (pin "A9") (pinfunction "SET5_A9") (pintype "passive"))
    )
    (net (code "261") (name "Net-(U10-CLKOUT0)") (class "Default")
      (node (ref "C42") (pin "1") (pinfunction "1_1") (pintype "passive"))
      (node (ref "U10") (pin "3") (pinfunction "CLKOUT0_3") (pintype "output"))
    )
    (net (code "262") (name "Net-(U10-CLKOUT1)") (class "Default")
      (node (ref "C43") (pin "1") (pinfunction "1_1") (pintype "passive"))
      (node (ref "U10") (pin "5") (pinfunction "CLKOUT1_5") (pintype "output"))
    )
    (net (code "263") (name "Net-(U10-CLKOUT2)") (class "Default")
      (node (ref "C44") (pin "1") (pinfunction "1_1") (pintype "passive"))
      (node (ref "U10") (pin "13") (pinfunction "CLKOUT2_13") (pintype "output"))
    )
    (net (code "264") (name "Net-(U10-CLKOUT3)") (class "Default")
      (node (ref "C45") (pin "1") (pinfunction "1_1") (pintype "passive"))
      (node (ref "U10") (pin "15") (pinfunction "CLKOUT3_15") (pintype "output"))
    )
    (net (code "265") (name "VCC_3p3_CARD") (class "Default")
      (node (ref "C34") (pin "2") (pinfunction "2_2") (pintype "passive"))
      (node (ref "C48") (pin "2") (pinfunction "2_2") (pintype "passive"))
      (node (ref "C49") (pin "2") (pinfunction "2_2") (pintype "passive"))
      (node (ref "C50") (pin "2") (pinfunction "2_2") (pintype "passive"))
      (node (ref "C51") (pin "2") (pinfunction "2_2") (pintype "passive"))
      (node (ref "J10") (pin "1") (pinfunction "1_1") (pintype "passive"))
      (node (ref "R11") (pin "2") (pinfunction "2_2") (pintype "passive"))
      (node (ref "SW1") (pin "6") (pinfunction "6_6") (pintype "passive"))
      (node (ref "U10") (pin "14") (pinfunction "VDDO_14") (pintype "power_in"))
      (node (ref "U10") (pin "18") (pinfunction "VDDO_18") (pintype "power_in"))
      (node (ref "U10") (pin "2") (pinfunction "VDDO_2") (pintype "power_in"))
      (node (ref "U10") (pin "6") (pinfunction "VDDO_6") (pintype "power_in"))
      (node (ref "U9") (pin "A10") (pinfunction "VOUT5_A10") (pintype "power_in"))
      (node (ref "U9") (pin "A11") (pinfunction "VOUT5_A11") (pintype "power_in"))
    )
    (net (code "266") (name "VCC_3p3_HOST") (class "Default")
      (node (ref "C46") (pin "2") (pinfunction "2_2") (pintype "passive"))
      (node (ref "C47") (pin "2") (pinfunction "2_2") (pintype "passive"))
      (node (ref "C52") (pin "2") (pinfunction "2_2") (pintype "passive"))
      (node (ref "C53") (pin "2") (pinfunction "2_2") (pintype "passive"))
      (node (ref "U10") (pin "23") (pinfunction "VDD_23") (pintype "power_in"))
      (node (ref "U10") (pin "24") (pinfunction "OE_24") (pintype "input"))
      (node (ref "U10") (pin "8") (pinfunction "VDD_8") (pintype "power_in"))
      (node (ref "U10") (pin "9") (pinfunction "OSCIN_9") (pintype "input"))
      (node (ref "U11") (pin "23") (pinfunction "VDD_23") (pintype "power_in"))
      (node (ref "U11") (pin "24") (pinfunction "OE_24") (pintype "input"))
      (node (ref "U11") (pin "8") (pinfunction "VDD_8") (pintype "power_in"))
      (node (ref "U11") (pin "9") (pinfunction "OSCIN_9") (pintype "input"))
    )
    (net (code "267") (name "VCC_3p3_Q0") (class "Default")
      (node (ref "C31") (pin "2") (pinfunction "2_2") (pintype "passive"))
      (node (ref "R8") (pin "2") (pinfunction "2_2") (pintype "passive"))
      (node (ref "U9") (pin "E11") (pinfunction "VOUT3_E11") (pintype "power_in"))
      (node (ref "U9") (pin "F11") (pinfunction "VOUT3_F11") (pintype "power_in"))
    )
    (net (code "268") (name "VCC_3p3_Q1") (class "Default")
      (node (ref "C30") (pin "2") (pinfunction "2_2") (pintype "passive"))
      (node (ref "R7") (pin "2") (pinfunction "2_2") (pintype "passive"))
      (node (ref "U9") (pin "J11") (pinfunction "VOUT2_J11") (pintype "power_in"))
      (node (ref "U9") (pin "K11") (pinfunction "VOUT2_K11") (pintype "power_in"))
    )
    (net (code "269") (name "VCC_3p3_Q2") (class "Default")
      (node (ref "C32") (pin "2") (pinfunction "2_2") (pintype "passive"))
      (node (ref "R10") (pin "2") (pinfunction "2_2") (pintype "passive"))
      (node (ref "U9") (pin "B11") (pinfunction "VOUT4_B11") (pintype "power_in"))
      (node (ref "U9") (pin "C11") (pinfunction "VOUT4_C11") (pintype "power_in"))
    )
    (net (code "270") (name "VCC_3p3_Q3") (class "Default")
      (node (ref "C29") (pin "2") (pinfunction "2_2") (pintype "passive"))
      (node (ref "R6") (pin "2") (pinfunction "2_2") (pintype "passive"))
      (node (ref "U9") (pin "L10") (pinfunction "VOUT1_L10") (pintype "power_in"))
      (node (ref "U9") (pin "L11") (pinfunction "VOUT1_L11") (pintype "power_in"))
    )
    (net (code "271") (name "VCC_12p0_CARD") (class "Default")
      (node (ref "C33") (pin "1") (pinfunction "1_1") (pintype "passive"))
      (node (ref "C58") (pin "1") (pinfunction "1_1") (pintype "passive"))
      (node (ref "J8") (pin "2") (pinfunction "12V_2") (pintype "power_in"))
      (node (ref "J9") (pin "2") (pinfunction "12V_2") (pintype "power_in"))
      (node (ref "R9") (pin "1") (pinfunction "1_1") (pintype "passive"))
      (node (ref "SW1") (pin "1") (pinfunction "1_1") (pintype "passive"))
      (node (ref "U9") (pin "A8") (pinfunction "BIAS45_A8") (pintype "input"))
      (node (ref "U9") (pin "B8") (pinfunction "BIAS123_B8") (pintype "input"))
      (node (ref "U9") (pin "J1") (pinfunction "VIN0_J1") (pintype "power_in"))
      (node (ref "U9") (pin "J2") (pinfunction "VIN0_J2") (pintype "power_in"))
      (node (ref "U9") (pin "J3") (pinfunction "VIN0_J3") (pintype "power_in"))
      (node (ref "U9") (pin "K1") (pinfunction "VIN0_K1") (pintype "power_in"))
      (node (ref "U9") (pin "K2") (pinfunction "VIN0_K2") (pintype "power_in"))
      (node (ref "U9") (pin "K3") (pinfunction "VIN0_K3") (pintype "power_in"))
      (node (ref "U9") (pin "L1") (pinfunction "VIN0_L1") (pintype "power_in"))
      (node (ref "U9") (pin "L2") (pinfunction "VIN0_L2") (pintype "power_in"))
      (node (ref "U9") (pin "L3") (pinfunction "VIN0_L3") (pintype "power_in"))
    )
    (net (code "272") (name "VCC_12p0_IN") (class "Default")
      (node (ref "J7") (pin "2") (pinfunction "PWR_2") (pintype "power_in"))
      (node (ref "R5") (pin "2") (pinfunction "2_2") (pintype "passive"))
      (node (ref "SW1") (pin "2") (pinfunction "2_2") (pintype "passive"))
    )
    (net (code "273") (name "VCC_VADJ_CARD") (class "Default")
      (node (ref "C54") (pin "2") (pinfunction "2_2") (pintype "passive"))
      (node (ref "C55") (pin "2") (pinfunction "2_2") (pintype "passive"))
      (node (ref "C56") (pin "2") (pinfunction "2_2") (pintype "passive"))
      (node (ref "C57") (pin "2") (pinfunction "2_2") (pintype "passive"))
      (node (ref "J12") (pin "1") (pinfunction "1_1") (pintype "passive"))
      (node (ref "U11") (pin "14") (pinfunction "VDDO_14") (pintype "power_in"))
      (node (ref "U11") (pin "18") (pinfunction "VDDO_18") (pintype "power_in"))
      (node (ref "U11") (pin "2") (pinfunction "VDDO_2") (pintype "power_in"))
      (node (ref "U11") (pin "6") (pinfunction "VDDO_6") (pintype "power_in"))
    )
    (net (code "274") (name "unconnected-(J8-TACH-Pad3)") (class "Default")
      (node (ref "J8") (pin "3") (pinfunction "TACH_3") (pintype "power_in"))
    )
    (net (code "275") (name "unconnected-(J9-TACH-Pad3)") (class "Default")
      (node (ref "J9") (pin "3") (pinfunction "TACH_3") (pintype "power_in"))
    )
    (net (code "276") (name "unconnected-(SW1-Pad3)") (class "Default")
      (node (ref "SW1") (pin "3") (pinfunction "3_3") (pintype "passive"))
    )
    (net (code "277") (name "unconnected-(U9B-COMP-PadL6)") (class "Default")
      (node (ref "U9") (pin "L6") (pinfunction "COMP_L6") (pintype "passive"))
    )
    (net (code "278") (name "unconnected-(U9B-SS-PadK4)") (class "Default")
      (node (ref "U9") (pin "K4") (pinfunction "SS_K4") (pintype "passive"))
    )
    (net (code "279") (name "unconnected-(U9B-SYNC-PadK7)") (class "Default")
      (node (ref "U9") (pin "K7") (pinfunction "SYNC_K7") (pintype "passive"))
    )
    (net (code "280") (name "unconnected-(U10-CLKOUT4-Pad17)") (class "Default")
      (node (ref "U10") (pin "17") (pinfunction "CLKOUT4_17") (pintype "output+no_connect"))
    )
    (net (code "281") (name "unconnected-(U10-OSCOUT-Pad10)") (class "Default")
      (node (ref "U10") (pin "10") (pinfunction "OSCOUT_10") (pintype "output+no_connect"))
    )
    (net (code "282") (name "unconnected-(U11-CLKOUT4-Pad17)") (class "Default")
      (node (ref "U11") (pin "17") (pinfunction "CLKOUT4_17") (pintype "output+no_connect"))
    )
    (net (code "283") (name "unconnected-(U11-OSCOUT-Pad10)") (class "Default")
      (node (ref "U11") (pin "10") (pinfunction "OSCOUT_10") (pintype "output+no_connect"))
    )
  )
)
